# board.net
KiCad netlist of a schematic drawn in EAGLE
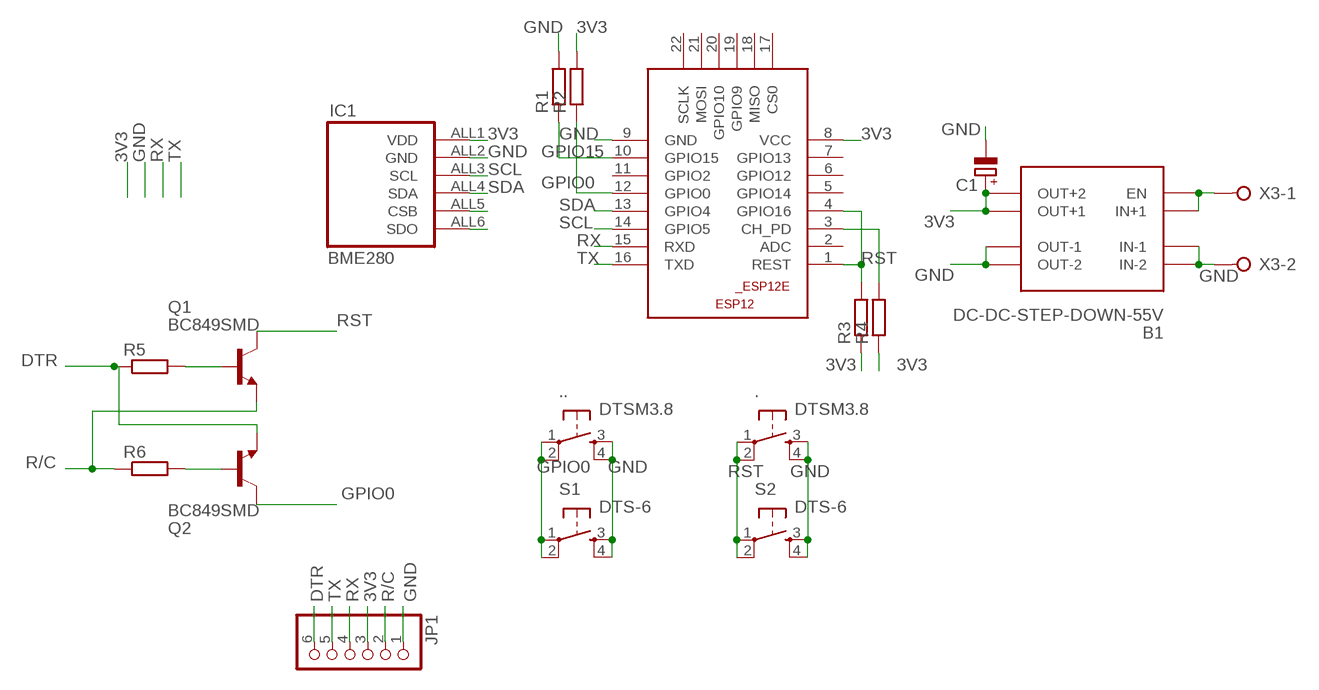
[diagram p0: schematic, sheet 1]

(export (version "E")
  (design (tool "Eeschema 10.0.6"))
  (components
    (comp (ref ".")
      (value "DTSM3.8")
      (footprint "eagle-import:DTSM3.8")
      (libsource (lib "eagle-import") (part "DTSM3.8"))
    )
    (comp (ref "..")
      (value "DTSM3.8")
      (footprint "eagle-import:DTSM3.8")
      (libsource (lib "eagle-import") (part "DTSM3.8"))
    )
    (comp (ref "B1")
      (value "DC-DC-STEP-DOWN-55V")
      (footprint "eagle-import:DC-DC-STEP-DOWN-55V")
      (libsource (lib "eagle-import") (part "DC-DC-STEP-DOWN-55V"))
    )
    (comp (ref "C1")
      (value "CPOL-EUE1.8-4")
      (footprint "eagle-import:E1,8-4")
      (libsource (lib "eagle-import") (part "CPOL-EUE1.8-4"))
    )
    (comp (ref "ESP12")
      (value "ESP8266-12EESP12E")
      (footprint "eagle-import:ESP8266-ESP12E")
      (libsource (lib "eagle-import") (part "ESP8266-12EESP12E"))
    )
    (comp (ref "IC1")
      (value "BME280")
      (footprint "eagle-import:BME280")
      (libsource (lib "eagle-import") (part "BME280"))
    )
    (comp (ref "JP1")
      (value "PINHD-1X6/90")
      (footprint "eagle-import:1X06_90")
      (libsource (lib "eagle-import") (part "PINHD-1X6/90"))
    )
    (comp (ref "Q1")
      (value "BC849SMD")
      (footprint "eagle-import:SOT23-BEC")
      (libsource (lib "eagle-import") (part "BC849SMD"))
    )
    (comp (ref "Q2")
      (value "BC849SMD")
      (footprint "eagle-import:SOT23-BEC")
      (libsource (lib "eagle-import") (part "BC849SMD"))
    )
    (comp (ref "R1")
      (value "R-EU_R1206")
      (footprint "eagle-import:R1206")
      (libsource (lib "eagle-import") (part "R-EU_R1206"))
    )
    (comp (ref "R2")
      (value "R-EU_R1206")
      (footprint "eagle-import:R1206")
      (libsource (lib "eagle-import") (part "R-EU_R1206"))
    )
    (comp (ref "R3")
      (value "R-EU_0207/10")
      (footprint "eagle-import:0207_10")
      (libsource (lib "eagle-import") (part "R-EU_0207/10"))
    )
    (comp (ref "R4")
      (value "R-EU_0207/10")
      (footprint "eagle-import:0207_10")
      (libsource (lib "eagle-import") (part "R-EU_0207/10"))
    )
    (comp (ref "R5")
      (value "R-EU_R1206")
      (footprint "eagle-import:R1206")
      (libsource (lib "eagle-import") (part "R-EU_R1206"))
    )
    (comp (ref "R6")
      (value "R-EU_R1206")
      (footprint "eagle-import:R1206")
      (libsource (lib "eagle-import") (part "R-EU_R1206"))
    )
    (comp (ref "S1")
      (value "DTS-6")
      (footprint "eagle-import:DTS-6")
      (libsource (lib "eagle-import") (part "DTS-6"))
    )
    (comp (ref "S2")
      (value "DTS-6")
      (footprint "eagle-import:DTS-6")
      (libsource (lib "eagle-import") (part "DTS-6"))
    )
    (comp (ref "X3")
      (value "W237-02P")
      (footprint "eagle-import:W237-132")
      (libsource (lib "eagle-import") (part "W237-02P"))
    )
  )
  (nets
    (net (code "1") (name "/3V3") (class "Default")
      (node (ref "B1") (pin "VOUT+1") (pinfunction "OUT+1_VOUT+1") (pintype "bidirectional"))
      (node (ref "B1") (pin "VOUT+2") (pinfunction "OUT+2_VOUT+2") (pintype "bidirectional"))
      (node (ref "C1") (pin "+") (pinfunction "+_+") (pintype "passive"))
      (node (ref "ESP12") (pin "8") (pinfunction "VCC_8") (pintype "bidirectional"))
      (node (ref "IC1") (pin "ALL1") (pinfunction "VDD_ALL1") (pintype "power_in"))
      (node (ref "JP1") (pin "3") (pinfunction "3_3") (pintype "passive"))
      (node (ref "R2") (pin "2") (pinfunction "2_2") (pintype "passive"))
      (node (ref "R3") (pin "1") (pinfunction "1_1") (pintype "passive"))
      (node (ref "R4") (pin "1") (pinfunction "1_1") (pintype "passive"))
    )
    (net (code "2") (name "/DTR") (class "Default")
      (node (ref "JP1") (pin "6") (pinfunction "6_6") (pintype "passive"))
      (node (ref "Q2") (pin "E") (pinfunction "E_E") (pintype "passive"))
      (node (ref "R5") (pin "1") (pinfunction "1_1") (pintype "passive"))
    )
    (net (code "3") (name "/GND") (class "Default")
      (node (ref ".") (pin "3") (pinfunction "3_3") (pintype "passive"))
      (node (ref ".") (pin "4") (pinfunction "4_4") (pintype "passive"))
      (node (ref "..") (pin "3") (pinfunction "3_3") (pintype "passive"))
      (node (ref "..") (pin "4") (pinfunction "4_4") (pintype "passive"))
      (node (ref "B1") (pin "VIN-1") (pinfunction "IN-1_VIN-1") (pintype "bidirectional"))
      (node (ref "B1") (pin "VIN-2") (pinfunction "IN-2_VIN-2") (pintype "bidirectional"))
      (node (ref "B1") (pin "VOUT-1") (pinfunction "OUT-1_VOUT-1") (pintype "bidirectional"))
      (node (ref "B1") (pin "VOUT-2") (pinfunction "OUT-2_VOUT-2") (pintype "bidirectional"))
      (node (ref "C1") (pin "-") (pinfunction "-_-") (pintype "passive"))
      (node (ref "ESP12") (pin "9") (pinfunction "GND_9") (pintype "bidirectional"))
      (node (ref "IC1") (pin "ALL2") (pinfunction "GND_ALL2") (pintype "power_in"))
      (node (ref "JP1") (pin "1") (pinfunction "1_1") (pintype "passive"))
      (node (ref "R1") (pin "2") (pinfunction "2_2") (pintype "passive"))
      (node (ref "S1") (pin "3") (pinfunction "3_3") (pintype "passive"))
      (node (ref "S1") (pin "4") (pinfunction "4_4") (pintype "passive"))
      (node (ref "S2") (pin "3") (pinfunction "3_3") (pintype "passive"))
      (node (ref "S2") (pin "4") (pinfunction "4_4") (pintype "passive"))
      (node (ref "X3") (pin "2") (pinfunction "KL_2") (pintype "passive"))
    )
    (net (code "4") (name "/GPIO0") (class "Default")
      (node (ref "..") (pin "1") (pinfunction "1_1") (pintype "passive"))
      (node (ref "..") (pin "2") (pinfunction "2_2") (pintype "passive"))
      (node (ref "ESP12") (pin "12") (pinfunction "GPIO0_12") (pintype "bidirectional"))
      (node (ref "Q2") (pin "C") (pinfunction "C_C") (pintype "passive"))
      (node (ref "R2") (pin "1") (pinfunction "1_1") (pintype "passive"))
      (node (ref "S1") (pin "1") (pinfunction "1_1") (pintype "passive"))
      (node (ref "S1") (pin "2") (pinfunction "2_2") (pintype "passive"))
    )
    (net (code "5") (name "/GPIO15") (class "Default")
      (node (ref "ESP12") (pin "10") (pinfunction "GPIO15_10") (pintype "bidirectional"))
      (node (ref "R1") (pin "1") (pinfunction "1_1") (pintype "passive"))
    )
    (net (code "6") (name "/RST") (class "Default")
      (node (ref ".") (pin "1") (pinfunction "1_1") (pintype "passive"))
      (node (ref ".") (pin "2") (pinfunction "2_2") (pintype "passive"))
      (node (ref "ESP12") (pin "1") (pinfunction "REST_1") (pintype "bidirectional"))
      (node (ref "ESP12") (pin "4") (pinfunction "GPIO16_4") (pintype "bidirectional"))
      (node (ref "Q1") (pin "C") (pinfunction "C_C") (pintype "passive"))
      (node (ref "R3") (pin "2") (pinfunction "2_2") (pintype "passive"))
      (node (ref "S2") (pin "1") (pinfunction "1_1") (pintype "passive"))
      (node (ref "S2") (pin "2") (pinfunction "2_2") (pintype "passive"))
    )
    (net (code "7") (name "/RX") (class "Default")
      (node (ref "ESP12") (pin "15") (pinfunction "RXD_15") (pintype "bidirectional"))
      (node (ref "JP1") (pin "4") (pinfunction "4_4") (pintype "passive"))
    )
    (net (code "8") (name "/R{slash}C") (class "Default")
      (node (ref "JP1") (pin "2") (pinfunction "2_2") (pintype "passive"))
      (node (ref "Q1") (pin "E") (pinfunction "E_E") (pintype "passive"))
      (node (ref "R6") (pin "1") (pinfunction "1_1") (pintype "passive"))
    )
    (net (code "9") (name "/SCL") (class "Default")
      (node (ref "ESP12") (pin "14") (pinfunction "GPIO5_14") (pintype "bidirectional"))
      (node (ref "IC1") (pin "ALL3") (pinfunction "SCL_ALL3") (pintype "bidirectional"))
    )
    (net (code "10") (name "/SDA") (class "Default")
      (node (ref "ESP12") (pin "13") (pinfunction "GPIO4_13") (pintype "bidirectional"))
      (node (ref "IC1") (pin "ALL4") (pinfunction "SDA_ALL4") (pintype "bidirectional"))
    )
    (net (code "11") (name "/TX") (class "Default")
      (node (ref "ESP12") (pin "16") (pinfunction "TXD_16") (pintype "bidirectional"))
      (node (ref "JP1") (pin "5") (pinfunction "5_5") (pintype "passive"))
    )
    (net (code "12") (name "Net-(B1-IN+1)") (class "Default")
      (node (ref "B1") (pin "EN") (pinfunction "EN_EN") (pintype "bidirectional"))
      (node (ref "B1") (pin "VIN+") (pinfunction "IN+1_VIN+") (pintype "bidirectional"))
      (node (ref "X3") (pin "1") (pinfunction "KL_1") (pintype "passive"))
    )
    (net (code "13") (name "Net-(ESP12-CH_PD)") (class "Default")
      (node (ref "ESP12") (pin "3") (pinfunction "CH_PD_3") (pintype "bidirectional"))
      (node (ref "R4") (pin "2") (pinfunction "2_2") (pintype "passive"))
    )
    (net (code "14") (name "Net-(Q1-PadB)") (class "Default")
      (node (ref "Q1") (pin "B") (pinfunction "B_B") (pintype "passive"))
      (node (ref "R5") (pin "2") (pinfunction "2_2") (pintype "passive"))
    )
    (net (code "15") (name "Net-(Q2-PadB)") (class "Default")
      (node (ref "Q2") (pin "B") (pinfunction "B_B") (pintype "passive"))
      (node (ref "R6") (pin "2") (pinfunction "2_2") (pintype "passive"))
    )
    (net (code "16") (name "unconnected-(ESP12-ADC-Pad2)") (class "Default")
      (node (ref "ESP12") (pin "2") (pinfunction "ADC_2") (pintype "bidirectional"))
    )
    (net (code "17") (name "unconnected-(ESP12-CS0-Pad17)") (class "Default")
      (node (ref "ESP12") (pin "17") (pinfunction "CS0_17") (pintype "bidirectional"))
    )
    (net (code "18") (name "unconnected-(ESP12-GPIO2-Pad11)") (class "Default")
      (node (ref "ESP12") (pin "11") (pinfunction "GPIO2_11") (pintype "bidirectional"))
    )
    (net (code "19") (name "unconnected-(ESP12-GPIO9-Pad19)") (class "Default")
      (node (ref "ESP12") (pin "19") (pinfunction "GPIO9_19") (pintype "bidirectional"))
    )
    (net (code "20") (name "unconnected-(ESP12-GPIO10-Pad20)") (class "Default")
      (node (ref "ESP12") (pin "20") (pinfunction "GPIO10_20") (pintype "bidirectional"))
    )
    (net (code "21") (name "unconnected-(ESP12-GPIO12-Pad6)") (class "Default")
      (node (ref "ESP12") (pin "6") (pinfunction "GPIO12_6") (pintype "bidirectional"))
    )
    (net (code "22") (name "unconnected-(ESP12-GPIO13-Pad7)") (class "Default")
      (node (ref "ESP12") (pin "7") (pinfunction "GPIO13_7") (pintype "bidirectional"))
    )
    (net (code "23") (name "unconnected-(ESP12-GPIO14-Pad5)") (class "Default")
      (node (ref "ESP12") (pin "5") (pinfunction "GPIO14_5") (pintype "bidirectional"))
    )
    (net (code "24") (name "unconnected-(ESP12-MISO-Pad18)") (class "Default")
      (node (ref "ESP12") (pin "18") (pinfunction "MISO_18") (pintype "bidirectional"))
    )
    (net (code "25") (name "unconnected-(ESP12-MOSI-Pad21)") (class "Default")
      (node (ref "ESP12") (pin "21") (pinfunction "MOSI_21") (pintype "bidirectional"))
    )
    (net (code "26") (name "unconnected-(ESP12-SCLK-Pad22)") (class "Default")
      (node (ref "ESP12") (pin "22") (pinfunction "SCLK_22") (pintype "bidirectional"))
    )
    (net (code "27") (name "unconnected-(IC1-CSB-PadALL5)") (class "Default")
      (node (ref "IC1") (pin "ALL5") (pinfunction "CSB_ALL5") (pintype "input"))
    )
    (net (code "28") (name "unconnected-(IC1-SDO-PadALL6)") (class "Default")
      (node (ref "IC1") (pin "ALL6") (pinfunction "SDO_ALL6") (pintype "input"))
    )
  )
)
